# AJH_2b_v1_01.net
KiCad netlist of a schematic drawn in EAGLE
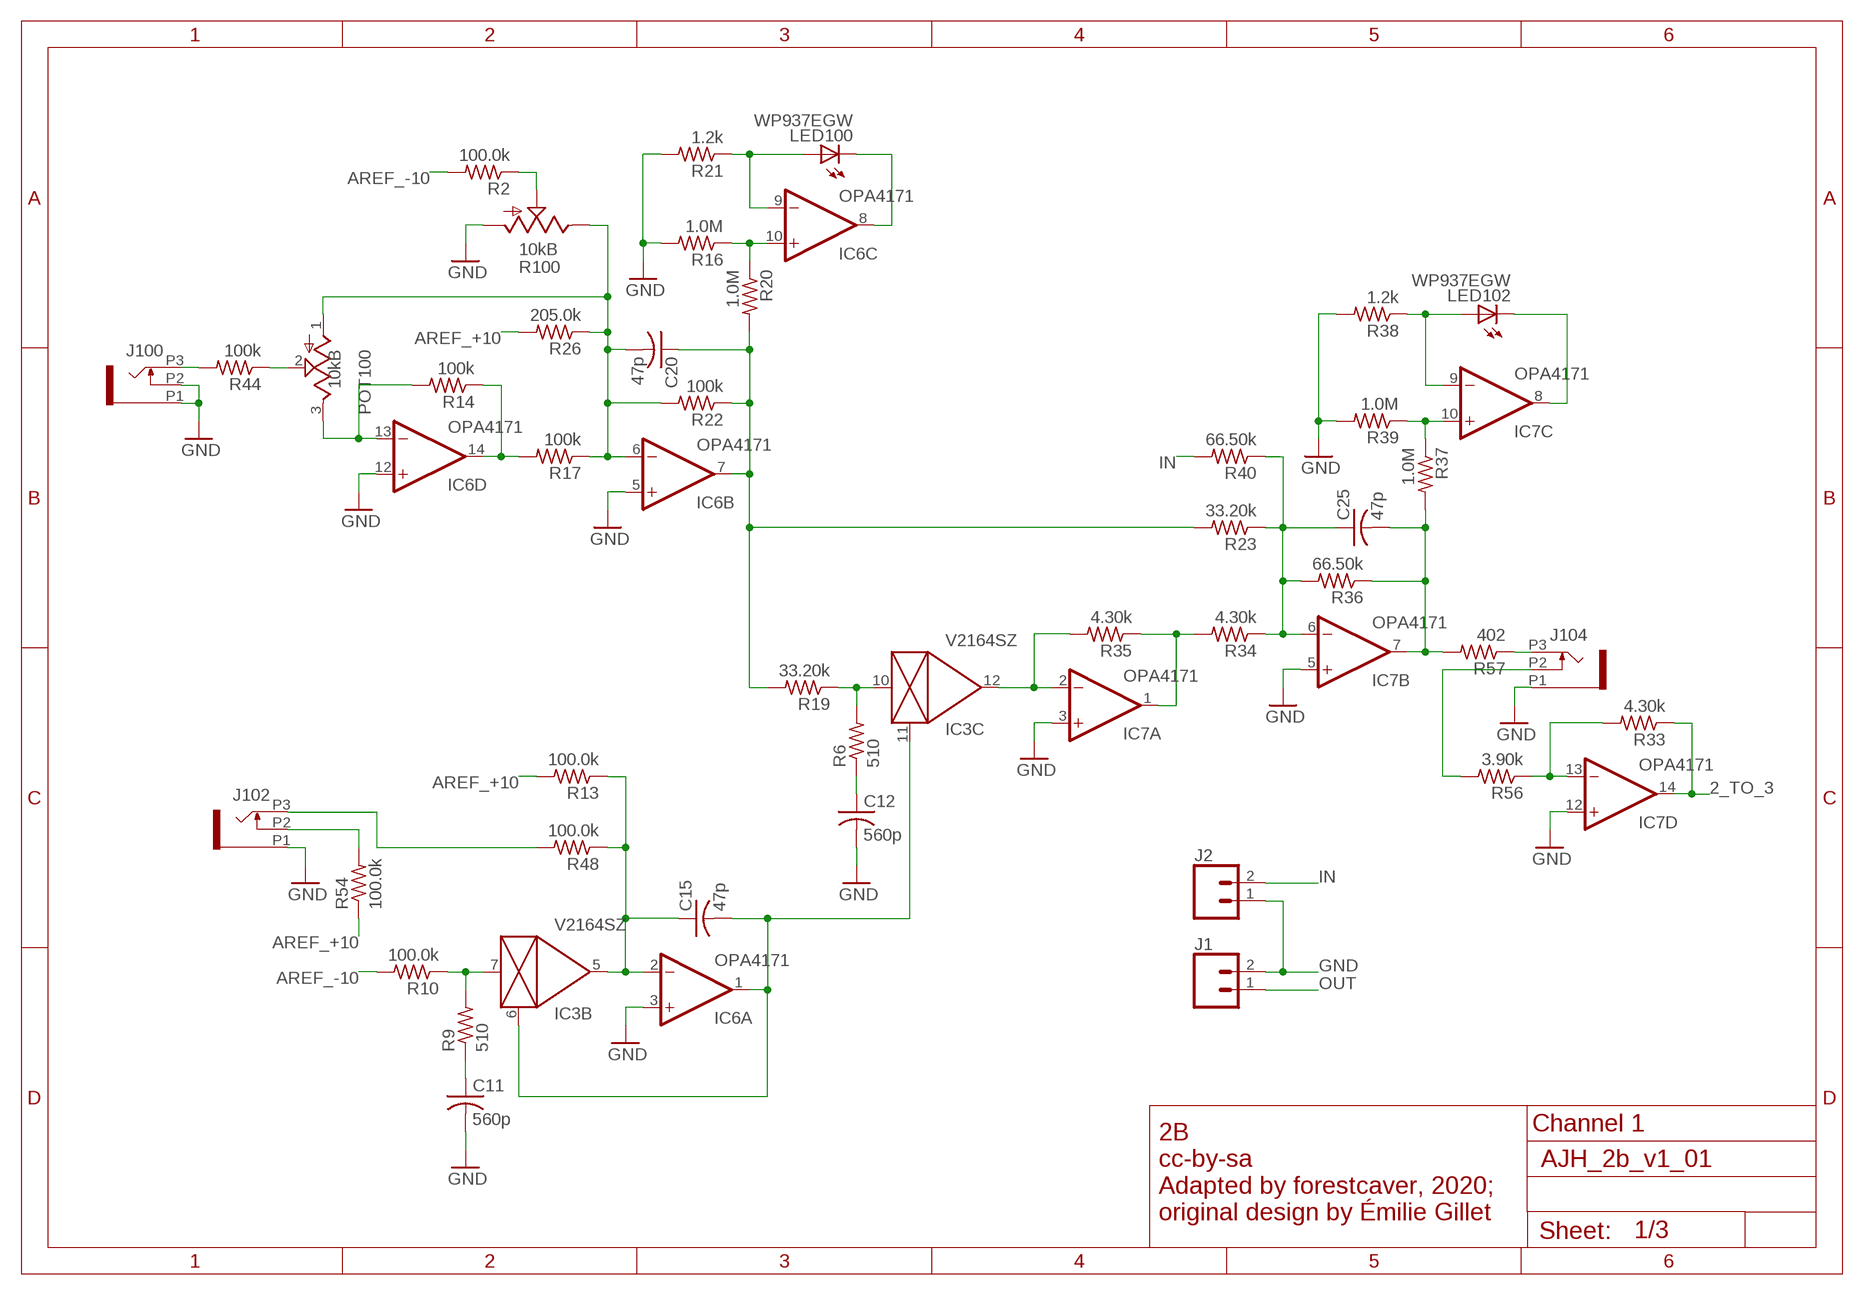
[diagram p0: schematic, sheet 1]
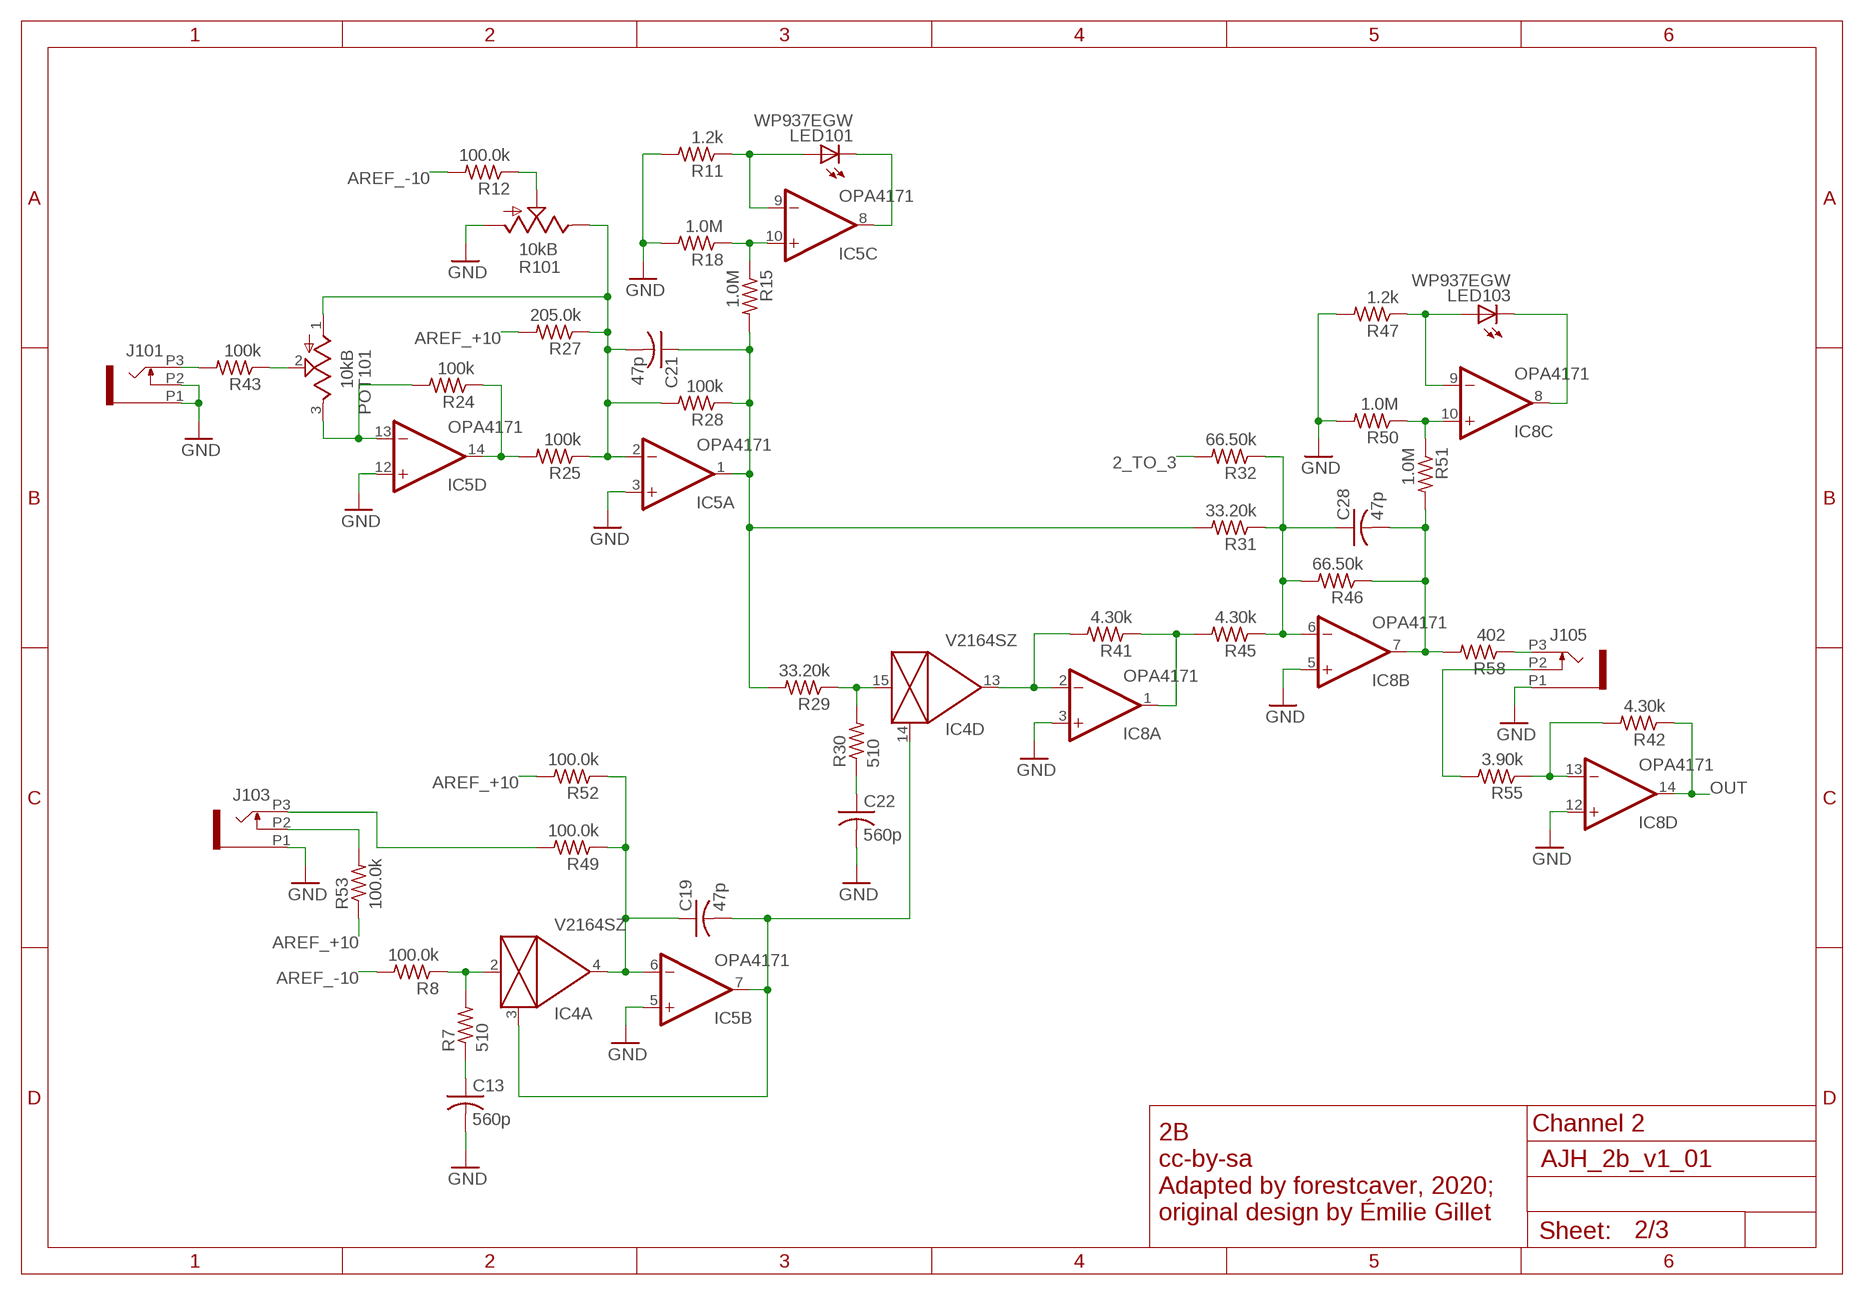
[diagram p1: schematic, sheet 2]
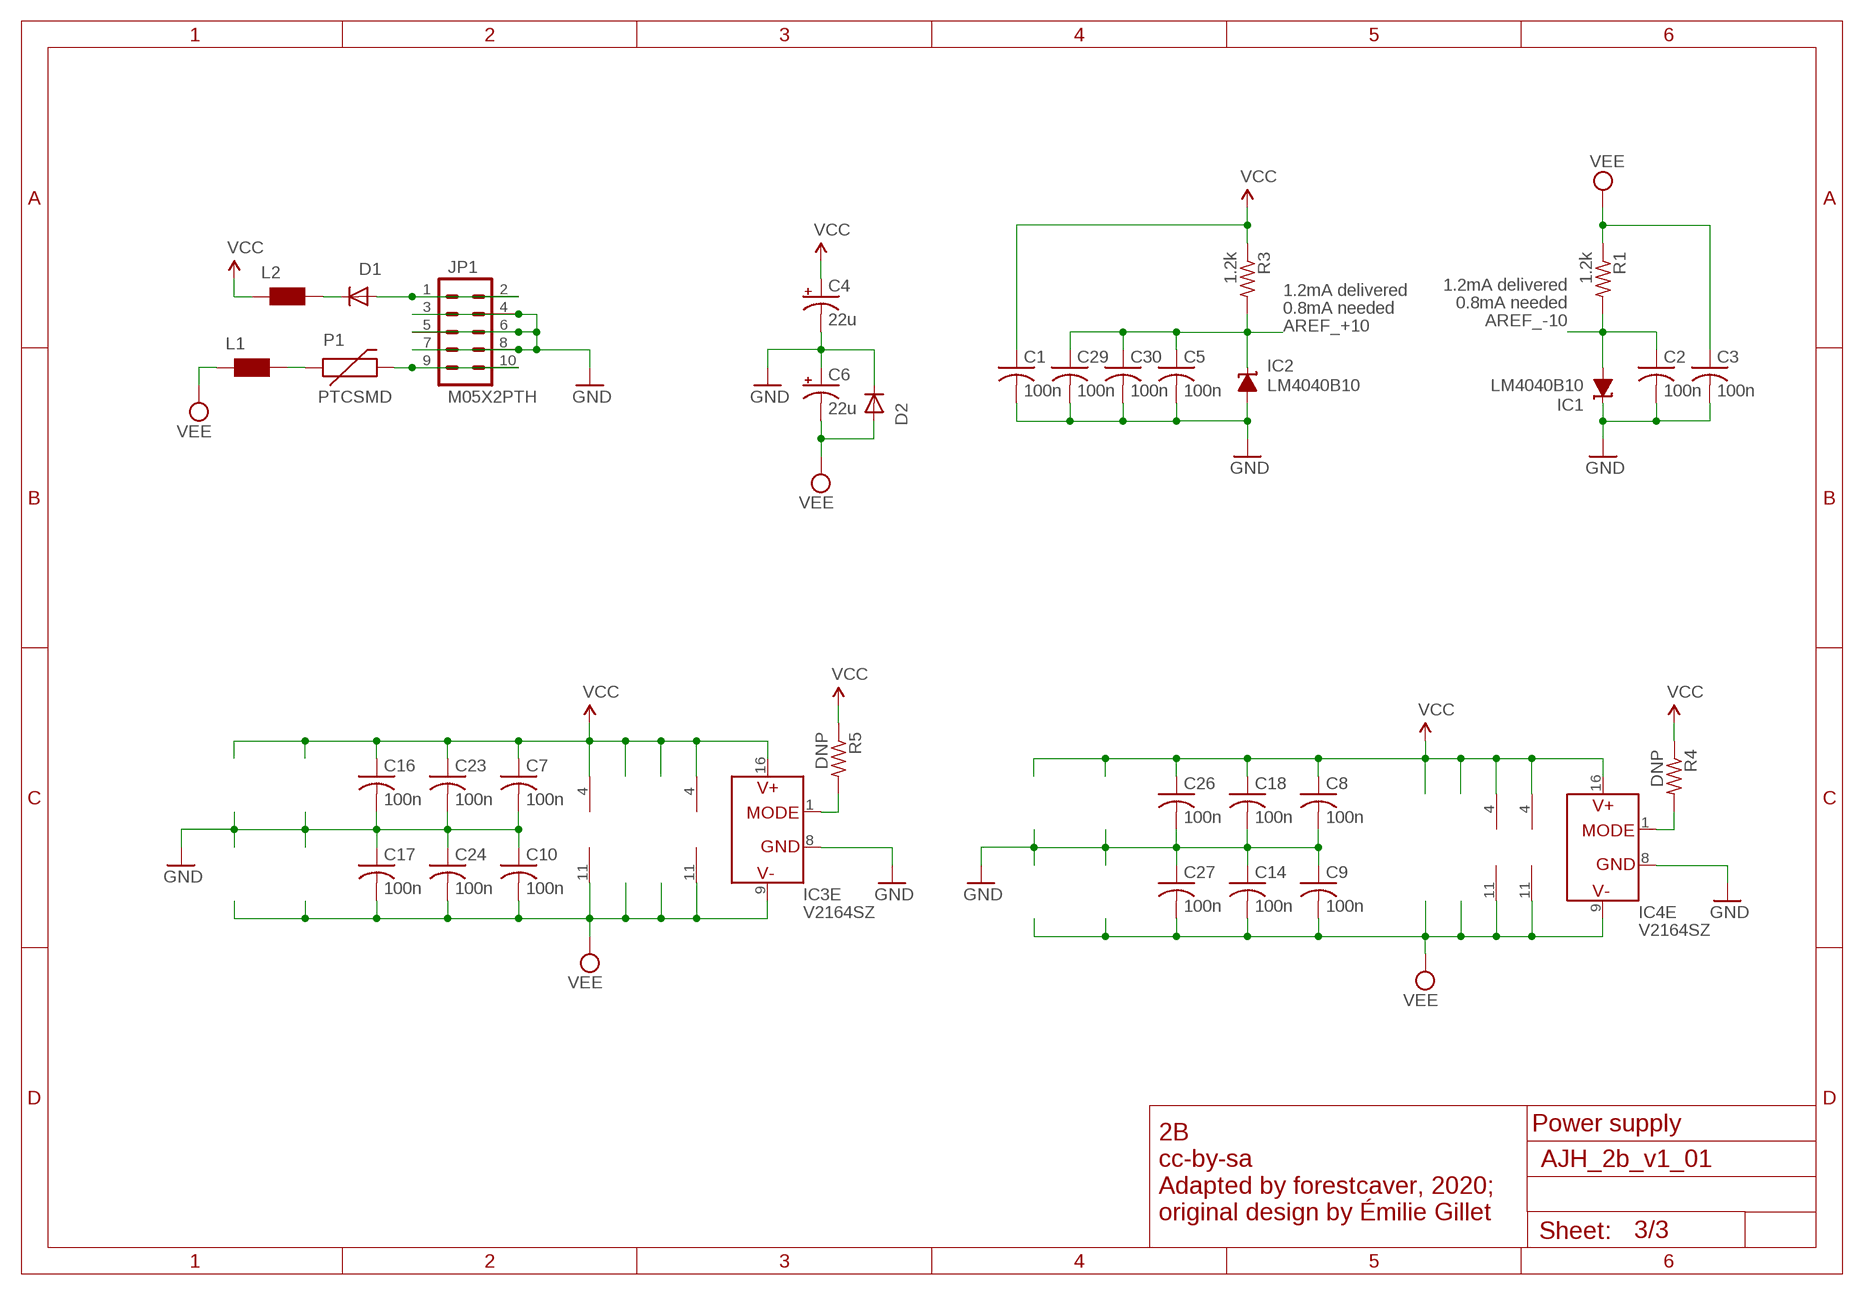
[diagram p2: schematic, sheet 3]

(export (version "E")
  (design (tool "Eeschema 10.0.6"))
  (components
    (comp (ref "C13")
      (value "560p")
      (footprint "eagle-import:C0402")
      (libsource (lib "eagle-import") (part "C-USC0402"))
    )
    (comp (ref "C19")
      (value "47p")
      (footprint "eagle-import:C0402")
      (libsource (lib "eagle-import") (part "C-USC0402"))
    )
    (comp (ref "C21")
      (value "47p")
      (footprint "eagle-import:C0402")
      (libsource (lib "eagle-import") (part "C-USC0402"))
    )
    (comp (ref "C22")
      (value "560p")
      (footprint "eagle-import:C0402")
      (libsource (lib "eagle-import") (part "C-USC0402"))
    )
    (comp (ref "C28")
      (value "47p")
      (footprint "eagle-import:C0402")
      (libsource (lib "eagle-import") (part "C-USC0402"))
    )
    (comp (ref "IC4")
      (value "V2164SZ")
      (footprint "eagle-import:SOIC16N")
      (libsource (lib "eagle-import") (part "SSM2164S"))
    )
    (comp (ref "IC5")
      (value "OPA4171")
      (footprint "eagle-import:TSSOP14")
      (libsource (lib "eagle-import") (part "TL074PW"))
    )
    (comp (ref "IC8")
      (value "OPA4171")
      (footprint "eagle-import:TSSOP14")
      (libsource (lib "eagle-import") (part "TL074PW"))
    )
    (comp (ref "J101")
      (value "PJ301_THONKICONN6")
      (footprint "eagle-import:WQP_PJ_301M6")
      (libsource (lib "eagle-import") (part "PJ301_THONKICONN6"))
    )
    (comp (ref "J103")
      (value "PJ301_THONKICONN6")
      (footprint "eagle-import:WQP_PJ_301M6")
      (libsource (lib "eagle-import") (part "PJ301_THONKICONN6"))
    )
    (comp (ref "J105")
      (value "PJ301_THONKICONN6")
      (footprint "eagle-import:WQP_PJ_301M6")
      (libsource (lib "eagle-import") (part "PJ301_THONKICONN6"))
    )
    (comp (ref "LED101")
      (value "WP937EGW")
      (footprint "eagle-import:LED3MM")
      (libsource (lib "eagle-import") (part "LED3MM"))
    )
    (comp (ref "LED103")
      (value "WP937EGW")
      (footprint "eagle-import:LED3MM")
      (libsource (lib "eagle-import") (part "LED3MM"))
    )
    (comp (ref "POT101")
      (value "10kB")
      (footprint "eagle-import:ALPS_POT_NOHOLE")
      (libsource (lib "eagle-import") (part "POT_VERTICALNOHOLE"))
    )
    (comp (ref "R7")
      (value "510")
      (footprint "eagle-import:R0402")
      (libsource (lib "eagle-import") (part "R-US_R0402"))
    )
    (comp (ref "R8")
      (value "100.0k")
      (footprint "eagle-import:R0402")
      (libsource (lib "eagle-import") (part "R-US_R0402"))
    )
    (comp (ref "R11")
      (value "1.2k")
      (footprint "eagle-import:R0402")
      (libsource (lib "eagle-import") (part "R-US_R0402"))
    )
    (comp (ref "R12")
      (value "100.0k")
      (footprint "eagle-import:R0402")
      (libsource (lib "eagle-import") (part "R-US_R0402"))
    )
    (comp (ref "R15")
      (value "1.0M")
      (footprint "eagle-import:R0402")
      (libsource (lib "eagle-import") (part "R-US_R0402"))
    )
    (comp (ref "R18")
      (value "1.0M")
      (footprint "eagle-import:R0402")
      (libsource (lib "eagle-import") (part "R-US_R0402"))
    )
    (comp (ref "R24")
      (value "100k")
      (footprint "eagle-import:R0402")
      (libsource (lib "eagle-import") (part "R-US_R0402"))
    )
    (comp (ref "R25")
      (value "100k")
      (footprint "eagle-import:R0402")
      (libsource (lib "eagle-import") (part "R-US_R0402"))
    )
    (comp (ref "R27")
      (value "205.0k")
      (footprint "eagle-import:R0402")
      (libsource (lib "eagle-import") (part "R-US_R0402"))
    )
    (comp (ref "R28")
      (value "100k")
      (footprint "eagle-import:R0402")
      (libsource (lib "eagle-import") (part "R-US_R0402"))
    )
    (comp (ref "R29")
      (value "33.20k")
      (footprint "eagle-import:R0402")
      (libsource (lib "eagle-import") (part "R-US_R0402"))
    )
    (comp (ref "R30")
      (value "510")
      (footprint "eagle-import:R0402")
      (libsource (lib "eagle-import") (part "R-US_R0402"))
    )
    (comp (ref "R31")
      (value "33.20k")
      (footprint "eagle-import:R0402")
      (libsource (lib "eagle-import") (part "R-US_R0402"))
    )
    (comp (ref "R32")
      (value "66.50k")
      (footprint "eagle-import:R0402")
      (libsource (lib "eagle-import") (part "R-US_R0402"))
    )
    (comp (ref "R41")
      (value "4.30k")
      (footprint "eagle-import:R0402")
      (libsource (lib "eagle-import") (part "R-US_R0402"))
    )
    (comp (ref "R42")
      (value "4.30k")
      (footprint "eagle-import:R0402")
      (libsource (lib "eagle-import") (part "R-US_R0402"))
    )
    (comp (ref "R43")
      (value "100k")
      (footprint "eagle-import:R0402")
      (libsource (lib "eagle-import") (part "R-US_R0402"))
    )
    (comp (ref "R45")
      (value "4.30k")
      (footprint "eagle-import:R0402")
      (libsource (lib "eagle-import") (part "R-US_R0402"))
    )
    (comp (ref "R46")
      (value "66.50k")
      (footprint "eagle-import:R0402")
      (libsource (lib "eagle-import") (part "R-US_R0402"))
    )
    (comp (ref "R47")
      (value "1.2k")
      (footprint "eagle-import:R0402")
      (libsource (lib "eagle-import") (part "R-US_R0402"))
    )
    (comp (ref "R49")
      (value "100.0k")
      (footprint "eagle-import:R0402")
      (libsource (lib "eagle-import") (part "R-US_R0402"))
    )
    (comp (ref "R50")
      (value "1.0M")
      (footprint "eagle-import:R0402")
      (libsource (lib "eagle-import") (part "R-US_R0402"))
    )
    (comp (ref "R51")
      (value "1.0M")
      (footprint "eagle-import:R0402")
      (libsource (lib "eagle-import") (part "R-US_R0402"))
    )
    (comp (ref "R52")
      (value "100.0k")
      (footprint "eagle-import:R0402")
      (libsource (lib "eagle-import") (part "R-US_R0402"))
    )
    (comp (ref "R53")
      (value "100.0k")
      (footprint "eagle-import:R0402")
      (libsource (lib "eagle-import") (part "R-US_R0402"))
    )
    (comp (ref "R55")
      (value "3.90k")
      (footprint "eagle-import:R0402")
      (libsource (lib "eagle-import") (part "R-US_R0402"))
    )
    (comp (ref "R58")
      (value "402")
      (footprint "eagle-import:R0402")
      (libsource (lib "eagle-import") (part "R-US_R0402"))
    )
    (comp (ref "R101")
      (value "10kB")
      (footprint "eagle-import:ALPS_POT_VERTICAL_PS")
      (libsource (lib "eagle-import") (part "POT_USVERTICAL_PS"))
    )
    (comp (ref "C11")
      (value "560p")
      (footprint "eagle-import:C0402")
      (libsource (lib "eagle-import") (part "C-USC0402"))
    )
    (comp (ref "C12")
      (value "560p")
      (footprint "eagle-import:C0402")
      (libsource (lib "eagle-import") (part "C-USC0402"))
    )
    (comp (ref "C15")
      (value "47p")
      (footprint "eagle-import:C0402")
      (libsource (lib "eagle-import") (part "C-USC0402"))
    )
    (comp (ref "C20")
      (value "47p")
      (footprint "eagle-import:C0402")
      (libsource (lib "eagle-import") (part "C-USC0402"))
    )
    (comp (ref "C25")
      (value "47p")
      (footprint "eagle-import:C0402")
      (libsource (lib "eagle-import") (part "C-USC0402"))
    )
    (comp (ref "IC3")
      (value "V2164SZ")
      (footprint "eagle-import:SOIC16N")
      (libsource (lib "eagle-import") (part "SSM2164S"))
    )
    (comp (ref "IC6")
      (value "OPA4171")
      (footprint "eagle-import:TSSOP14")
      (libsource (lib "eagle-import") (part "TL074PW"))
    )
    (comp (ref "IC7")
      (value "OPA4171")
      (footprint "eagle-import:TSSOP14")
      (libsource (lib "eagle-import") (part "TL074PW"))
    )
    (comp (ref "J1")
      (value "CONN_02")
      (footprint "eagle-import:1X02")
      (libsource (lib "eagle-import") (part "CONN_02"))
    )
    (comp (ref "J2")
      (value "CONN_02")
      (footprint "eagle-import:1X02")
      (libsource (lib "eagle-import") (part "CONN_02"))
    )
    (comp (ref "J100")
      (value "PJ301_THONKICONN6")
      (footprint "eagle-import:WQP_PJ_301M6")
      (libsource (lib "eagle-import") (part "PJ301_THONKICONN6"))
    )
    (comp (ref "J102")
      (value "PJ301_THONKICONN6")
      (footprint "eagle-import:WQP_PJ_301M6")
      (libsource (lib "eagle-import") (part "PJ301_THONKICONN6"))
    )
    (comp (ref "J104")
      (value "PJ301_THONKICONN6")
      (footprint "eagle-import:WQP_PJ_301M6")
      (libsource (lib "eagle-import") (part "PJ301_THONKICONN6"))
    )
    (comp (ref "LED100")
      (value "WP937EGW")
      (footprint "eagle-import:LED3MM")
      (libsource (lib "eagle-import") (part "LED3MM"))
    )
    (comp (ref "LED102")
      (value "WP937EGW")
      (footprint "eagle-import:LED3MM")
      (libsource (lib "eagle-import") (part "LED3MM"))
    )
    (comp (ref "POT100")
      (value "10kB")
      (footprint "eagle-import:ALPS_POT_NOHOLE")
      (libsource (lib "eagle-import") (part "POT_VERTICALNOHOLE"))
    )
    (comp (ref "R2")
      (value "100.0k")
      (footprint "eagle-import:R0402")
      (libsource (lib "eagle-import") (part "R-US_R0402"))
    )
    (comp (ref "R6")
      (value "510")
      (footprint "eagle-import:R0402")
      (libsource (lib "eagle-import") (part "R-US_R0402"))
    )
    (comp (ref "R9")
      (value "510")
      (footprint "eagle-import:R0402")
      (libsource (lib "eagle-import") (part "R-US_R0402"))
    )
    (comp (ref "R10")
      (value "100.0k")
      (footprint "eagle-import:R0402")
      (libsource (lib "eagle-import") (part "R-US_R0402"))
    )
    (comp (ref "R13")
      (value "100.0k")
      (footprint "eagle-import:R0402")
      (libsource (lib "eagle-import") (part "R-US_R0402"))
    )
    (comp (ref "R14")
      (value "100k")
      (footprint "eagle-import:R0402")
      (libsource (lib "eagle-import") (part "R-US_R0402"))
    )
    (comp (ref "R16")
      (value "1.0M")
      (footprint "eagle-import:R0402")
      (libsource (lib "eagle-import") (part "R-US_R0402"))
    )
    (comp (ref "R17")
      (value "100k")
      (footprint "eagle-import:R0402")
      (libsource (lib "eagle-import") (part "R-US_R0402"))
    )
    (comp (ref "R19")
      (value "33.20k")
      (footprint "eagle-import:R0402")
      (libsource (lib "eagle-import") (part "R-US_R0402"))
    )
    (comp (ref "R20")
      (value "1.0M")
      (footprint "eagle-import:R0402")
      (libsource (lib "eagle-import") (part "R-US_R0402"))
    )
    (comp (ref "R21")
      (value "1.2k")
      (footprint "eagle-import:R0402")
      (libsource (lib "eagle-import") (part "R-US_R0402"))
    )
    (comp (ref "R22")
      (value "100k")
      (footprint "eagle-import:R0402")
      (libsource (lib "eagle-import") (part "R-US_R0402"))
    )
    (comp (ref "R23")
      (value "33.20k")
      (footprint "eagle-import:R0402")
      (libsource (lib "eagle-import") (part "R-US_R0402"))
    )
    (comp (ref "R26")
      (value "205.0k")
      (footprint "eagle-import:R0402")
      (libsource (lib "eagle-import") (part "R-US_R0402"))
    )
    (comp (ref "R33")
      (value "4.30k")
      (footprint "eagle-import:R0402")
      (libsource (lib "eagle-import") (part "R-US_R0402"))
    )
    (comp (ref "R34")
      (value "4.30k")
      (footprint "eagle-import:R0402")
      (libsource (lib "eagle-import") (part "R-US_R0402"))
    )
    (comp (ref "R35")
      (value "4.30k")
      (footprint "eagle-import:R0402")
      (libsource (lib "eagle-import") (part "R-US_R0402"))
    )
    (comp (ref "R36")
      (value "66.50k")
      (footprint "eagle-import:R0402")
      (libsource (lib "eagle-import") (part "R-US_R0402"))
    )
    (comp (ref "R37")
      (value "1.0M")
      (footprint "eagle-import:R0402")
      (libsource (lib "eagle-import") (part "R-US_R0402"))
    )
    (comp (ref "R38")
      (value "1.2k")
      (footprint "eagle-import:R0402")
      (libsource (lib "eagle-import") (part "R-US_R0402"))
    )
    (comp (ref "R39")
      (value "1.0M")
      (footprint "eagle-import:R0402")
      (libsource (lib "eagle-import") (part "R-US_R0402"))
    )
    (comp (ref "R40")
      (value "66.50k")
      (footprint "eagle-import:R0402")
      (libsource (lib "eagle-import") (part "R-US_R0402"))
    )
    (comp (ref "R44")
      (value "100k")
      (footprint "eagle-import:R0402")
      (libsource (lib "eagle-import") (part "R-US_R0402"))
    )
    (comp (ref "R48")
      (value "100.0k")
      (footprint "eagle-import:R0402")
      (libsource (lib "eagle-import") (part "R-US_R0402"))
    )
    (comp (ref "R54")
      (value "100.0k")
      (footprint "eagle-import:R0402")
      (libsource (lib "eagle-import") (part "R-US_R0402"))
    )
    (comp (ref "R56")
      (value "3.90k")
      (footprint "eagle-import:R0402")
      (libsource (lib "eagle-import") (part "R-US_R0402"))
    )
    (comp (ref "R57")
      (value "402")
      (footprint "eagle-import:R0402")
      (libsource (lib "eagle-import") (part "R-US_R0402"))
    )
    (comp (ref "R100")
      (value "10kB")
      (footprint "eagle-import:ALPS_POT_VERTICAL_PS")
      (libsource (lib "eagle-import") (part "POT_USVERTICAL_PS"))
    )
    (comp (ref "C1")
      (value "100n")
      (footprint "eagle-import:C0402")
      (libsource (lib "eagle-import") (part "C-USC0402"))
    )
    (comp (ref "C2")
      (value "100n")
      (footprint "eagle-import:C0402")
      (libsource (lib "eagle-import") (part "C-USC0402"))
    )
    (comp (ref "C3")
      (value "100n")
      (footprint "eagle-import:C0402")
      (libsource (lib "eagle-import") (part "C-USC0402"))
    )
    (comp (ref "C4")
      (value "22u")
      (footprint "eagle-import:PANASONIC_B")
      (libsource (lib "eagle-import") (part "CPOL-USB"))
    )
    (comp (ref "C5")
      (value "100n")
      (footprint "eagle-import:C0402")
      (libsource (lib "eagle-import") (part "C-USC0402"))
    )
    (comp (ref "C6")
      (value "22u")
      (footprint "eagle-import:PANASONIC_B")
      (libsource (lib "eagle-import") (part "CPOL-USB"))
    )
    (comp (ref "C7")
      (value "100n")
      (footprint "eagle-import:C0402")
      (libsource (lib "eagle-import") (part "C-USC0402"))
    )
    (comp (ref "C8")
      (value "100n")
      (footprint "eagle-import:C0402")
      (libsource (lib "eagle-import") (part "C-USC0402"))
    )
    (comp (ref "C9")
      (value "100n")
      (footprint "eagle-import:C0402")
      (libsource (lib "eagle-import") (part "C-USC0402"))
    )
    (comp (ref "C10")
      (value "100n")
      (footprint "eagle-import:C0402")
      (libsource (lib "eagle-import") (part "C-USC0402"))
    )
    (comp (ref "C14")
      (value "100n")
      (footprint "eagle-import:C0402")
      (libsource (lib "eagle-import") (part "C-USC0402"))
    )
    (comp (ref "C16")
      (value "100n")
      (footprint "eagle-import:C0402")
      (libsource (lib "eagle-import") (part "C-USC0402"))
    )
    (comp (ref "C17")
      (value "100n")
      (footprint "eagle-import:C0402")
      (libsource (lib "eagle-import") (part "C-USC0402"))
    )
    (comp (ref "C18")
      (value "100n")
      (footprint "eagle-import:C0402")
      (libsource (lib "eagle-import") (part "C-USC0402"))
    )
    (comp (ref "C23")
      (value "100n")
      (footprint "eagle-import:C0402")
      (libsource (lib "eagle-import") (part "C-USC0402"))
    )
    (comp (ref "C24")
      (value "100n")
      (footprint "eagle-import:C0402")
      (libsource (lib "eagle-import") (part "C-USC0402"))
    )
    (comp (ref "C26")
      (value "100n")
      (footprint "eagle-import:C0402")
      (libsource (lib "eagle-import") (part "C-USC0402"))
    )
    (comp (ref "C27")
      (value "100n")
      (footprint "eagle-import:C0402")
      (libsource (lib "eagle-import") (part "C-USC0402"))
    )
    (comp (ref "C29")
      (value "100n")
      (footprint "eagle-import:C0402")
      (libsource (lib "eagle-import") (part "C-USC0402"))
    )
    (comp (ref "C30")
      (value "100n")
      (footprint "eagle-import:C0402")
      (libsource (lib "eagle-import") (part "C-USC0402"))
    )
    (comp (ref "D1")
      (value "1N5819HW")
      (footprint "eagle-import:SOD123")
      (libsource (lib "eagle-import") (part "DIODE-SOD123"))
    )
    (comp (ref "D2")
      (value "1N5819HW")
      (footprint "eagle-import:SOD123")
      (libsource (lib "eagle-import") (part "DIODE-SOD123"))
    )
    (comp (ref "IC1")
      (value "LM4040B10")
      (footprint "eagle-import:DBZ_R-PDSO-G3")
      (libsource (lib "eagle-import") (part "LM4041DBZB12"))
    )
    (comp (ref "IC2")
      (value "LM4040B10")
      (footprint "eagle-import:DBZ_R-PDSO-G3")
      (libsource (lib "eagle-import") (part "LM4041DBZB12"))
    )
    (comp (ref "JP1")
      (value "M05X2PTH")
      (footprint "eagle-import:AVR_ICSP")
      (libsource (lib "eagle-import") (part "M05X2PTH"))
    )
    (comp (ref "L1")
      (value "WE-CBF_0603")
      (footprint "eagle-import:0603")
      (libsource (lib "eagle-import") (part "WE-CBF_0603"))
    )
    (comp (ref "L2")
      (value "WE-CBF_0603")
      (footprint "eagle-import:0603")
      (libsource (lib "eagle-import") (part "WE-CBF_0603"))
    )
    (comp (ref "P1")
      (value "PTCSMD")
      (footprint "eagle-import:PTC-1206")
      (libsource (lib "eagle-import") (part "PTCSMD"))
    )
    (comp (ref "R1")
      (value "1.2k")
      (footprint "eagle-import:R0402")
      (libsource (lib "eagle-import") (part "R-US_R0402"))
    )
    (comp (ref "R3")
      (value "1.2k")
      (footprint "eagle-import:R0402")
      (libsource (lib "eagle-import") (part "R-US_R0402"))
    )
    (comp (ref "R4")
      (value "DNP")
      (footprint "eagle-import:R0402")
      (libsource (lib "eagle-import") (part "R-US_R0402"))
    )
    (comp (ref "R5")
      (value "DNP")
      (footprint "eagle-import:R0402")
      (libsource (lib "eagle-import") (part "R-US_R0402"))
    )
  )
  (nets
    (net (code "1") (name "2_TO_3") (class "Default")
      (node (ref "IC7") (pin "14") (pinfunction "OUT_14") (pintype "output"))
      (node (ref "R32") (pin "2") (pinfunction "2_2") (pintype "passive"))
      (node (ref "R33") (pin "1") (pinfunction "1_1") (pintype "passive"))
    )
    (net (code "2") (name "AREF_+10") (class "Default")
      (node (ref "C29") (pin "1") (pinfunction "1_1") (pintype "passive"))
      (node (ref "C30") (pin "1") (pinfunction "1_1") (pintype "passive"))
      (node (ref "C5") (pin "1") (pinfunction "1_1") (pintype "passive"))
      (node (ref "IC2") (pin "1") (pinfunction "C_1") (pintype "passive"))
      (node (ref "R13") (pin "2") (pinfunction "2_2") (pintype "passive"))
      (node (ref "R26") (pin "2") (pinfunction "2_2") (pintype "passive"))
      (node (ref "R27") (pin "2") (pinfunction "2_2") (pintype "passive"))
      (node (ref "R3") (pin "2") (pinfunction "2_2") (pintype "passive"))
      (node (ref "R52") (pin "2") (pinfunction "2_2") (pintype "passive"))
      (node (ref "R53") (pin "1") (pinfunction "1_1") (pintype "passive"))
      (node (ref "R54") (pin "1") (pinfunction "1_1") (pintype "passive"))
    )
    (net (code "3") (name "AREF_-10") (class "Default")
      (node (ref "C2") (pin "1") (pinfunction "1_1") (pintype "passive"))
      (node (ref "IC1") (pin "2") (pinfunction "A_2") (pintype "passive"))
      (node (ref "R1") (pin "2") (pinfunction "2_2") (pintype "passive"))
      (node (ref "R10") (pin "2") (pinfunction "2_2") (pintype "passive"))
      (node (ref "R12") (pin "2") (pinfunction "2_2") (pintype "passive"))
      (node (ref "R2") (pin "2") (pinfunction "2_2") (pintype "passive"))
      (node (ref "R8") (pin "2") (pinfunction "2_2") (pintype "passive"))
    )
    (net (code "4") (name "GND") (class "Default")
      (node (ref "C1") (pin "2") (pinfunction "2_2") (pintype "passive"))
      (node (ref "C10") (pin "1") (pinfunction "1_1") (pintype "passive"))
      (node (ref "C11") (pin "2") (pinfunction "2_2") (pintype "passive"))
      (node (ref "C12") (pin "2") (pinfunction "2_2") (pintype "passive"))
      (node (ref "C13") (pin "2") (pinfunction "2_2") (pintype "passive"))
      (node (ref "C14") (pin "1") (pinfunction "1_1") (pintype "passive"))
      (node (ref "C16") (pin "2") (pinfunction "2_2") (pintype "passive"))
      (node (ref "C17") (pin "1") (pinfunction "1_1") (pintype "passive"))
      (node (ref "C18") (pin "2") (pinfunction "2_2") (pintype "passive"))
      (node (ref "C2") (pin "2") (pinfunction "2_2") (pintype "passive"))
      (node (ref "C22") (pin "2") (pinfunction "2_2") (pintype "passive"))
      (node (ref "C23") (pin "2") (pinfunction "2_2") (pintype "passive"))
      (node (ref "C24") (pin "1") (pinfunction "1_1") (pintype "passive"))
      (node (ref "C26") (pin "2") (pinfunction "2_2") (pintype "passive"))
      (node (ref "C27") (pin "1") (pinfunction "1_1") (pintype "passive"))
      (node (ref "C29") (pin "2") (pinfunction "2_2") (pintype "passive"))
      (node (ref "C3") (pin "2") (pinfunction "2_2") (pintype "passive"))
      (node (ref "C30") (pin "2") (pinfunction "2_2") (pintype "passive"))
      (node (ref "C4") (pin "-") (pinfunction "-_-") (pintype "passive"))
      (node (ref "C5") (pin "2") (pinfunction "2_2") (pintype "passive"))
      (node (ref "C6") (pin "+") (pinfunction "+_+") (pintype "passive"))
      (node (ref "C7") (pin "2") (pinfunction "2_2") (pintype "passive"))
      (node (ref "C8") (pin "2") (pinfunction "2_2") (pintype "passive"))
      (node (ref "C9") (pin "1") (pinfunction "1_1") (pintype "passive"))
      (node (ref "D2") (pin "C") (pinfunction "C_C") (pintype "passive"))
      (node (ref "IC1") (pin "1") (pinfunction "C_1") (pintype "passive"))
      (node (ref "IC2") (pin "2") (pinfunction "A_2") (pintype "passive"))
      (node (ref "IC3") (pin "8") (pinfunction "GND_8") (pintype "power_in"))
      (node (ref "IC4") (pin "8") (pinfunction "GND_8") (pintype "power_in"))
      (node (ref "IC5") (pin "12") (pinfunction "+IN_12") (pintype "input"))
      (node (ref "IC5") (pin "3") (pinfunction "+IN_3") (pintype "input"))
      (node (ref "IC5") (pin "5") (pinfunction "+IN_5") (pintype "input"))
      (node (ref "IC6") (pin "12") (pinfunction "+IN_12") (pintype "input"))
      (node (ref "IC6") (pin "3") (pinfunction "+IN_3") (pintype "input"))
      (node (ref "IC6") (pin "5") (pinfunction "+IN_5") (pintype "input"))
      (node (ref "IC7") (pin "12") (pinfunction "+IN_12") (pintype "input"))
      (node (ref "IC7") (pin "3") (pinfunction "+IN_3") (pintype "input"))
      (node (ref "IC7") (pin "5") (pinfunction "+IN_5") (pintype "input"))
      (node (ref "IC8") (pin "12") (pinfunction "+IN_12") (pintype "input"))
      (node (ref "IC8") (pin "3") (pinfunction "+IN_3") (pintype "input"))
      (node (ref "IC8") (pin "5") (pinfunction "+IN_5") (pintype "input"))
      (node (ref "J1") (pin "2") (pinfunction "2_2") (pintype "passive"))
      (node (ref "J100") (pin "P1") (pinfunction "1_P1") (pintype "passive"))
      (node (ref "J100") (pin "P2") (pinfunction "2_P2") (pintype "passive"))
      (node (ref "J101") (pin "P1") (pinfunction "1_P1") (pintype "passive"))
      (node (ref "J101") (pin "P2") (pinfunction "2_P2") (pintype "passive"))
      (node (ref "J102") (pin "P1") (pinfunction "1_P1") (pintype "passive"))
      (node (ref "J103") (pin "P1") (pinfunction "1_P1") (pintype "passive"))
      (node (ref "J104") (pin "P1") (pinfunction "1_P1") (pintype "passive"))
      (node (ref "J105") (pin "P1") (pinfunction "1_P1") (pintype "passive"))
      (node (ref "J2") (pin "1") (pinfunction "1_1") (pintype "passive"))
      (node (ref "JP1") (pin "3") (pinfunction "3_3") (pintype "passive"))
      (node (ref "JP1") (pin "4") (pinfunction "4_4") (pintype "passive"))
      (node (ref "JP1") (pin "5") (pinfunction "5_5") (pintype "passive"))
      (node (ref "JP1") (pin "6") (pinfunction "6_6") (pintype "passive"))
      (node (ref "JP1") (pin "7") (pinfunction "7_7") (pintype "passive"))
      (node (ref "JP1") (pin "8") (pinfunction "8_8") (pintype "passive"))
      (node (ref "R100") (pin "P$3") (pinfunction "A_P$3") (pintype "passive"))
      (node (ref "R101") (pin "P$3") (pinfunction "A_P$3") (pintype "passive"))
      (node (ref "R11") (pin "2") (pinfunction "2_2") (pintype "passive"))
      (node (ref "R16") (pin "2") (pinfunction "2_2") (pintype "passive"))
      (node (ref "R18") (pin "2") (pinfunction "2_2") (pintype "passive"))
      (node (ref "R21") (pin "2") (pinfunction "2_2") (pintype "passive"))
      (node (ref "R38") (pin "2") (pinfunction "2_2") (pintype "passive"))
      (node (ref "R39") (pin "2") (pinfunction "2_2") (pintype "passive"))
      (node (ref "R47") (pin "2") (pinfunction "2_2") (pintype "passive"))
      (node (ref "R50") (pin "2") (pinfunction "2_2") (pintype "passive"))
    )
    (net (code "5") (name "IN") (class "Default")
      (node (ref "J2") (pin "2") (pinfunction "2_2") (pintype "passive"))
      (node (ref "R40") (pin "2") (pinfunction "2_2") (pintype "passive"))
    )
    (net (code "6") (name "Net-(C11-Pad1)") (class "Default")
      (node (ref "C11") (pin "1") (pinfunction "1_1") (pintype "passive"))
      (node (ref "R9") (pin "1") (pinfunction "1_1") (pintype "passive"))
    )
    (net (code "7") (name "Net-(C12-Pad1)") (class "Default")
      (node (ref "C12") (pin "1") (pinfunction "1_1") (pintype "passive"))
      (node (ref "R6") (pin "1") (pinfunction "1_1") (pintype "passive"))
    )
    (net (code "8") (name "Net-(C13-Pad1)") (class "Default")
      (node (ref "C13") (pin "1") (pinfunction "1_1") (pintype "passive"))
      (node (ref "R7") (pin "1") (pinfunction "1_1") (pintype "passive"))
    )
    (net (code "9") (name "Net-(C22-Pad1)") (class "Default")
      (node (ref "C22") (pin "1") (pinfunction "1_1") (pintype "passive"))
      (node (ref "R30") (pin "1") (pinfunction "1_1") (pintype "passive"))
    )
    (net (code "10") (name "Net-(D1-PadA)") (class "Default")
      (node (ref "D1") (pin "A") (pinfunction "A_A") (pintype "passive"))
      (node (ref "JP1") (pin "1") (pinfunction "1_1") (pintype "passive"))
      (node (ref "JP1") (pin "2") (pinfunction "2_2") (pintype "passive"))
    )
    (net (code "11") (name "Net-(D1-PadC)") (class "Default")
      (node (ref "D1") (pin "C") (pinfunction "C_C") (pintype "passive"))
      (node (ref "L2") (pin "2") (pinfunction "2_2") (pintype "passive"))
    )
    (net (code "12") (name "Net-(IC3B-CTRL)") (class "Default")
      (node (ref "C15") (pin "2") (pinfunction "2_2") (pintype "passive"))
      (node (ref "IC3") (pin "11") (pinfunction "CTRL_11") (pintype "input"))
      (node (ref "IC3") (pin "6") (pinfunction "CTRL_6") (pintype "input"))
      (node (ref "IC6") (pin "1") (pinfunction "OUT_1") (pintype "output"))
    )
    (net (code "13") (name "Net-(IC3B-IN)") (class "Default")
      (node (ref "IC3") (pin "7") (pinfunction "IN_7") (pintype "input"))
      (node (ref "R10") (pin "1") (pinfunction "1_1") (pintype "passive"))
      (node (ref "R9") (pin "2") (pinfunction "2_2") (pintype "passive"))
    )
    (net (code "14") (name "Net-(IC3B-OUT)") (class "Default")
      (node (ref "C15") (pin "1") (pinfunction "1_1") (pintype "passive"))
      (node (ref "IC3") (pin "5") (pinfunction "OUT_5") (pintype "output"))
      (node (ref "IC6") (pin "2") (pinfunction "-IN_2") (pintype "input"))
      (node (ref "R13") (pin "1") (pinfunction "1_1") (pintype "passive"))
      (node (ref "R48") (pin "1") (pinfunction "1_1") (pintype "passive"))
    )
    (net (code "15") (name "Net-(IC3C-IN)") (class "Default")
      (node (ref "IC3") (pin "10") (pinfunction "IN_10") (pintype "input"))
      (node (ref "R19") (pin "1") (pinfunction "1_1") (pintype "passive"))
      (node (ref "R6") (pin "2") (pinfunction "2_2") (pintype "passive"))
    )
    (net (code "16") (name "Net-(IC3C-OUT)") (class "Default")
      (node (ref "IC3") (pin "12") (pinfunction "OUT_12") (pintype "output"))
      (node (ref "IC7") (pin "2") (pinfunction "-IN_2") (pintype "input"))
      (node (ref "R35") (pin "2") (pinfunction "2_2") (pintype "passive"))
    )
    (net (code "17") (name "Net-(IC3E-MODE)") (class "Default")
      (node (ref "IC3") (pin "1") (pinfunction "MODE_1") (pintype "input"))
      (node (ref "R5") (pin "2") (pinfunction "2_2") (pintype "passive"))
    )
    (net (code "18") (name "Net-(IC4A-CTRL)") (class "Default")
      (node (ref "C19") (pin "2") (pinfunction "2_2") (pintype "passive"))
      (node (ref "IC4") (pin "14") (pinfunction "CTRL_14") (pintype "input"))
      (node (ref "IC4") (pin "3") (pinfunction "CTRL_3") (pintype "input"))
      (node (ref "IC5") (pin "7") (pinfunction "OUT_7") (pintype "output"))
    )
    (net (code "19") (name "Net-(IC4A-IN)") (class "Default")
      (node (ref "IC4") (pin "2") (pinfunction "IN_2") (pintype "input"))
      (node (ref "R7") (pin "2") (pinfunction "2_2") (pintype "passive"))
      (node (ref "R8") (pin "1") (pinfunction "1_1") (pintype "passive"))
    )
    (net (code "20") (name "Net-(IC4A-OUT)") (class "Default")
      (node (ref "C19") (pin "1") (pinfunction "1_1") (pintype "passive"))
      (node (ref "IC4") (pin "4") (pinfunction "OUT_4") (pintype "output"))
      (node (ref "IC5") (pin "6") (pinfunction "-IN_6") (pintype "input"))
      (node (ref "R49") (pin "1") (pinfunction "1_1") (pintype "passive"))
      (node (ref "R52") (pin "1") (pinfunction "1_1") (pintype "passive"))
    )
    (net (code "21") (name "Net-(IC4D-IN)") (class "Default")
      (node (ref "IC4") (pin "15") (pinfunction "IN_15") (pintype "input"))
      (node (ref "R29") (pin "1") (pinfunction "1_1") (pintype "passive"))
      (node (ref "R30") (pin "2") (pinfunction "2_2") (pintype "passive"))
    )
    (net (code "22") (name "Net-(IC4D-OUT)") (class "Default")
      (node (ref "IC4") (pin "13") (pinfunction "OUT_13") (pintype "output"))
      (node (ref "IC8") (pin "2") (pinfunction "-IN_2") (pintype "input"))
      (node (ref "R41") (pin "2") (pinfunction "2_2") (pintype "passive"))
    )
    (net (code "23") (name "Net-(IC4E-MODE)") (class "Default")
      (node (ref "IC4") (pin "1") (pinfunction "MODE_1") (pintype "input"))
      (node (ref "R4") (pin "2") (pinfunction "2_2") (pintype "passive"))
    )
    (net (code "24") (name "Net-(IC5A--IN)") (class "Default")
      (node (ref "C21") (pin "2") (pinfunction "2_2") (pintype "passive"))
      (node (ref "IC5") (pin "2") (pinfunction "-IN_2") (pintype "input"))
      (node (ref "POT101") (pin "1") (pinfunction "A_1") (pintype "passive"))
      (node (ref "R101") (pin "P$1") (pinfunction "E_P$1") (pintype "passive"))
      (node (ref "R25") (pin "1") (pinfunction "1_1") (pintype "passive"))
      (node (ref "R27") (pin "1") (pinfunction "1_1") (pintype "passive"))
      (node (ref "R28") (pin "2") (pinfunction "2_2") (pintype "passive"))
    )
    (net (code "25") (name "Net-(IC5A-OUT)") (class "Default")
      (node (ref "C21") (pin "1") (pinfunction "1_1") (pintype "passive"))
      (node (ref "IC5") (pin "1") (pinfunction "OUT_1") (pintype "output"))
      (node (ref "R15") (pin "2") (pinfunction "2_2") (pintype "passive"))
      (node (ref "R28") (pin "1") (pinfunction "1_1") (pintype "passive"))
      (node (ref "R29") (pin "2") (pinfunction "2_2") (pintype "passive"))
      (node (ref "R31") (pin "2") (pinfunction "2_2") (pintype "passive"))
    )
    (net (code "26") (name "Net-(IC5C-+IN)") (class "Default")
      (node (ref "IC5") (pin "10") (pinfunction "+IN_10") (pintype "input"))
      (node (ref "R15") (pin "1") (pinfunction "1_1") (pintype "passive"))
      (node (ref "R18") (pin "1") (pinfunction "1_1") (pintype "passive"))
    )
    (net (code "27") (name "Net-(IC5C--IN)") (class "Default")
      (node (ref "IC5") (pin "9") (pinfunction "-IN_9") (pintype "input"))
      (node (ref "LED101") (pin "A") (pinfunction "A_A") (pintype "passive"))
      (node (ref "R11") (pin "1") (pinfunction "1_1") (pintype "passive"))
    )
    (net (code "28") (name "Net-(IC5C-OUT)") (class "Default")
      (node (ref "IC5") (pin "8") (pinfunction "OUT_8") (pintype "output"))
      (node (ref "LED101") (pin "K") (pinfunction "C_K") (pintype "passive"))
    )
    (net (code "29") (name "Net-(IC5D--IN)") (class "Default")
      (node (ref "IC5") (pin "13") (pinfunction "-IN_13") (pintype "input"))
      (node (ref "POT101") (pin "3") (pinfunction "B_3") (pintype "passive"))
      (node (ref "R24") (pin "2") (pinfunction "2_2") (pintype "passive"))
    )
    (net (code "30") (name "Net-(IC5D-OUT)") (class "Default")
      (node (ref "IC5") (pin "14") (pinfunction "OUT_14") (pintype "output"))
      (node (ref "R24") (pin "1") (pinfunction "1_1") (pintype "passive"))
      (node (ref "R25") (pin "2") (pinfunction "2_2") (pintype "passive"))
    )
    (net (code "31") (name "Net-(IC6B--IN)") (class "Default")
      (node (ref "C20") (pin "2") (pinfunction "2_2") (pintype "passive"))
      (node (ref "IC6") (pin "6") (pinfunction "-IN_6") (pintype "input"))
      (node (ref "POT100") (pin "1") (pinfunction "A_1") (pintype "passive"))
      (node (ref "R100") (pin "P$1") (pinfunction "E_P$1") (pintype "passive"))
      (node (ref "R17") (pin "1") (pinfunction "1_1") (pintype "passive"))
      (node (ref "R22") (pin "2") (pinfunction "2_2") (pintype "passive"))
      (node (ref "R26") (pin "1") (pinfunction "1_1") (pintype "passive"))
    )
    (net (code "32") (name "Net-(IC6B-OUT)") (class "Default")
      (node (ref "C20") (pin "1") (pinfunction "1_1") (pintype "passive"))
      (node (ref "IC6") (pin "7") (pinfunction "OUT_7") (pintype "output"))
      (node (ref "R19") (pin "2") (pinfunction "2_2") (pintype "passive"))
      (node (ref "R20") (pin "2") (pinfunction "2_2") (pintype "passive"))
      (node (ref "R22") (pin "1") (pinfunction "1_1") (pintype "passive"))
      (node (ref "R23") (pin "2") (pinfunction "2_2") (pintype "passive"))
    )
    (net (code "33") (name "Net-(IC6C-+IN)") (class "Default")
      (node (ref "IC6") (pin "10") (pinfunction "+IN_10") (pintype "input"))
      (node (ref "R16") (pin "1") (pinfunction "1_1") (pintype "passive"))
      (node (ref "R20") (pin "1") (pinfunction "1_1") (pintype "passive"))
    )
    (net (code "34") (name "Net-(IC6C--IN)") (class "Default")
      (node (ref "IC6") (pin "9") (pinfunction "-IN_9") (pintype "input"))
      (node (ref "LED100") (pin "A") (pinfunction "A_A") (pintype "passive"))
      (node (ref "R21") (pin "1") (pinfunction "1_1") (pintype "passive"))
    )
    (net (code "35") (name "Net-(IC6C-OUT)") (class "Default")
      (node (ref "IC6") (pin "8") (pinfunction "OUT_8") (pintype "output"))
      (node (ref "LED100") (pin "K") (pinfunction "C_K") (pintype "passive"))
    )
    (net (code "36") (name "Net-(IC6D--IN)") (class "Default")
      (node (ref "IC6") (pin "13") (pinfunction "-IN_13") (pintype "input"))
      (node (ref "POT100") (pin "3") (pinfunction "B_3") (pintype "passive"))
      (node (ref "R14") (pin "2") (pinfunction "2_2") (pintype "passive"))
    )
    (net (code "37") (name "Net-(IC6D-OUT)") (class "Default")
      (node (ref "IC6") (pin "14") (pinfunction "OUT_14") (pintype "output"))
      (node (ref "R14") (pin "1") (pinfunction "1_1") (pintype "passive"))
      (node (ref "R17") (pin "2") (pinfunction "2_2") (pintype "passive"))
    )
    (net (code "38") (name "Net-(IC7A-OUT)") (class "Default")
      (node (ref "IC7") (pin "1") (pinfunction "OUT_1") (pintype "output"))
      (node (ref "R34") (pin "2") (pinfunction "2_2") (pintype "passive"))
      (node (ref "R35") (pin "1") (pinfunction "1_1") (pintype "passive"))
    )
    (net (code "39") (name "Net-(IC7B--IN)") (class "Default")
      (node (ref "C25") (pin "1") (pinfunction "1_1") (pintype "passive"))
      (node (ref "IC7") (pin "6") (pinfunction "-IN_6") (pintype "input"))
      (node (ref "R23") (pin "1") (pinfunction "1_1") (pintype "passive"))
      (node (ref "R34") (pin "1") (pinfunction "1_1") (pintype "passive"))
      (node (ref "R36") (pin "2") (pinfunction "2_2") (pintype "passive"))
      (node (ref "R40") (pin "1") (pinfunction "1_1") (pintype "passive"))
    )
    (net (code "40") (name "Net-(IC7B-OUT)") (class "Default")
      (node (ref "C25") (pin "2") (pinfunction "2_2") (pintype "passive"))
      (node (ref "IC7") (pin "7") (pinfunction "OUT_7") (pintype "output"))
      (node (ref "R36") (pin "1") (pinfunction "1_1") (pintype "passive"))
      (node (ref "R37") (pin "2") (pinfunction "2_2") (pintype "passive"))
      (node (ref "R57") (pin "2") (pinfunction "2_2") (pintype "passive"))
    )
    (net (code "41") (name "Net-(IC7C-+IN)") (class "Default")
      (node (ref "IC7") (pin "10") (pinfunction "+IN_10") (pintype "input"))
      (node (ref "R37") (pin "1") (pinfunction "1_1") (pintype "passive"))
      (node (ref "R39") (pin "1") (pinfunction "1_1") (pintype "passive"))
    )
    (net (code "42") (name "Net-(IC7C--IN)") (class "Default")
      (node (ref "IC7") (pin "9") (pinfunction "-IN_9") (pintype "input"))
      (node (ref "LED102") (pin "A") (pinfunction "A_A") (pintype "passive"))
      (node (ref "R38") (pin "1") (pinfunction "1_1") (pintype "passive"))
    )
    (net (code "43") (name "Net-(IC7C-OUT)") (class "Default")
      (node (ref "IC7") (pin "8") (pinfunction "OUT_8") (pintype "output"))
      (node (ref "LED102") (pin "K") (pinfunction "C_K") (pintype "passive"))
    )
    (net (code "44") (name "Net-(IC7D--IN)") (class "Default")
      (node (ref "IC7") (pin "13") (pinfunction "-IN_13") (pintype "input"))
      (node (ref "R33") (pin "2") (pinfunction "2_2") (pintype "passive"))
      (node (ref "R56") (pin "1") (pinfunction "1_1") (pintype "passive"))
    )
    (net (code "45") (name "Net-(IC8A-OUT)") (class "Default")
      (node (ref "IC8") (pin "1") (pinfunction "OUT_1") (pintype "output"))
      (node (ref "R41") (pin "1") (pinfunction "1_1") (pintype "passive"))
      (node (ref "R45") (pin "2") (pinfunction "2_2") (pintype "passive"))
    )
    (net (code "46") (name "Net-(IC8B--IN)") (class "Default")
      (node (ref "C28") (pin "1") (pinfunction "1_1") (pintype "passive"))
      (node (ref "IC8") (pin "6") (pinfunction "-IN_6") (pintype "input"))
      (node (ref "R31") (pin "1") (pinfunction "1_1") (pintype "passive"))
      (node (ref "R32") (pin "1") (pinfunction "1_1") (pintype "passive"))
      (node (ref "R45") (pin "1") (pinfunction "1_1") (pintype "passive"))
      (node (ref "R46") (pin "2") (pinfunction "2_2") (pintype "passive"))
    )
    (net (code "47") (name "Net-(IC8B-OUT)") (class "Default")
      (node (ref "C28") (pin "2") (pinfunction "2_2") (pintype "passive"))
      (node (ref "IC8") (pin "7") (pinfunction "OUT_7") (pintype "output"))
      (node (ref "R46") (pin "1") (pinfunction "1_1") (pintype "passive"))
      (node (ref "R51") (pin "2") (pinfunction "2_2") (pintype "passive"))
      (node (ref "R58") (pin "2") (pinfunction "2_2") (pintype "passive"))
    )
    (net (code "48") (name "Net-(IC8C-+IN)") (class "Default")
      (node (ref "IC8") (pin "10") (pinfunction "+IN_10") (pintype "input"))
      (node (ref "R50") (pin "1") (pinfunction "1_1") (pintype "passive"))
      (node (ref "R51") (pin "1") (pinfunction "1_1") (pintype "passive"))
    )
    (net (code "49") (name "Net-(IC8C--IN)") (class "Default")
      (node (ref "IC8") (pin "9") (pinfunction "-IN_9") (pintype "input"))
      (node (ref "LED103") (pin "A") (pinfunction "A_A") (pintype "passive"))
      (node (ref "R47") (pin "1") (pinfunction "1_1") (pintype "passive"))
    )
    (net (code "50") (name "Net-(IC8C-OUT)") (class "Default")
      (node (ref "IC8") (pin "8") (pinfunction "OUT_8") (pintype "output"))
      (node (ref "LED103") (pin "K") (pinfunction "C_K") (pintype "passive"))
    )
    (net (code "51") (name "Net-(IC8D--IN)") (class "Default")
      (node (ref "IC8") (pin "13") (pinfunction "-IN_13") (pintype "input"))
      (node (ref "R42") (pin "2") (pinfunction "2_2") (pintype "passive"))
      (node (ref "R55") (pin "1") (pinfunction "1_1") (pintype "passive"))
    )
    (net (code "52") (name "Net-(J100-3)") (class "Default")
      (node (ref "J100") (pin "P3") (pinfunction "3_P3") (pintype "passive"))
      (node (ref "R44") (pin "2") (pinfunction "2_2") (pintype "passive"))
    )
    (net (code "53") (name "Net-(J101-3)") (class "Default")
      (node (ref "J101") (pin "P3") (pinfunction "3_P3") (pintype "passive"))
      (node (ref "R43") (pin "2") (pinfunction "2_2") (pintype "passive"))
    )
    (net (code "54") (name "Net-(J102-2)") (class "Default")
      (node (ref "J102") (pin "P2") (pinfunction "2_P2") (pintype "passive"))
      (node (ref "R54") (pin "2") (pinfunction "2_2") (pintype "passive"))
    )
    (net (code "55") (name "Net-(J102-3)") (class "Default")
      (node (ref "J102") (pin "P3") (pinfunction "3_P3") (pintype "passive"))
      (node (ref "R48") (pin "2") (pinfunction "2_2") (pintype "passive"))
    )
    (net (code "56") (name "Net-(J103-2)") (class "Default")
      (node (ref "J103") (pin "P2") (pinfunction "2_P2") (pintype "passive"))
      (node (ref "R53") (pin "2") (pinfunction "2_2") (pintype "passive"))
    )
    (net (code "57") (name "Net-(J103-3)") (class "Default")
      (node (ref "J103") (pin "P3") (pinfunction "3_P3") (pintype "passive"))
      (node (ref "R49") (pin "2") (pinfunction "2_2") (pintype "passive"))
    )
    (net (code "58") (name "Net-(J104-2)") (class "Default")
      (node (ref "J104") (pin "P2") (pinfunction "2_P2") (pintype "passive"))
      (node (ref "R56") (pin "2") (pinfunction "2_2") (pintype "passive"))
    )
    (net (code "59") (name "Net-(J104-3)") (class "Default")
      (node (ref "J104") (pin "P3") (pinfunction "3_P3") (pintype "passive"))
      (node (ref "R57") (pin "1") (pinfunction "1_1") (pintype "passive"))
    )
    (net (code "60") (name "Net-(J105-2)") (class "Default")
      (node (ref "J105") (pin "P2") (pinfunction "2_P2") (pintype "passive"))
      (node (ref "R55") (pin "2") (pinfunction "2_2") (pintype "passive"))
    )
    (net (code "61") (name "Net-(J105-3)") (class "Default")
      (node (ref "J105") (pin "P3") (pinfunction "3_P3") (pintype "passive"))
      (node (ref "R58") (pin "1") (pinfunction "1_1") (pintype "passive"))
    )
    (net (code "62") (name "Net-(JP1-Pad10)") (class "Default")
      (node (ref "JP1") (pin "10") (pinfunction "10_10") (pintype "passive"))
      (node (ref "JP1") (pin "9") (pinfunction "9_9") (pintype "passive"))
      (node (ref "P1") (pin "2") (pinfunction "2_2") (pintype "bidirectional"))
    )
    (net (code "63") (name "Net-(L1-Pad2)") (class "Default")
      (node (ref "L1") (pin "2") (pinfunction "2_2") (pintype "passive"))
      (node (ref "P1") (pin "1") (pinfunction "1_1") (pintype "bidirectional"))
    )
    (net (code "64") (name "Net-(POT100-W)") (class "Default")
      (node (ref "POT100") (pin "2") (pinfunction "W_2") (pintype "passive"))
      (node (ref "R44") (pin "1") (pinfunction "1_1") (pintype "passive"))
    )
    (net (code "65") (name "Net-(POT101-W)") (class "Default")
      (node (ref "POT101") (pin "2") (pinfunction "W_2") (pintype "passive"))
      (node (ref "R43") (pin "1") (pinfunction "1_1") (pintype "passive"))
    )
    (net (code "66") (name "Net-(R100-S)") (class "Default")
      (node (ref "R100") (pin "P$2") (pinfunction "S_P$2") (pintype "passive"))
      (node (ref "R2") (pin "1") (pinfunction "1_1") (pintype "passive"))
    )
    (net (code "67") (name "Net-(R101-S)") (class "Default")
      (node (ref "R101") (pin "P$2") (pinfunction "S_P$2") (pintype "passive"))
      (node (ref "R12") (pin "1") (pinfunction "1_1") (pintype "passive"))
    )
    (net (code "68") (name "OUT") (class "Default")
      (node (ref "IC8") (pin "14") (pinfunction "OUT_14") (pintype "output"))
      (node (ref "J1") (pin "1") (pinfunction "1_1") (pintype "passive"))
      (node (ref "R42") (pin "1") (pinfunction "1_1") (pintype "passive"))
    )
    (net (code "69") (name "VCC") (class "Default")
      (node (ref "C1") (pin "1") (pinfunction "1_1") (pintype "passive"))
      (node (ref "C16") (pin "1") (pinfunction "1_1") (pintype "passive"))
      (node (ref "C18") (pin "1") (pinfunction "1_1") (pintype "passive"))
      (node (ref "C23") (pin "1") (pinfunction "1_1") (pintype "passive"))
      (node (ref "C26") (pin "1") (pinfunction "1_1") (pintype "passive"))
      (node (ref "C4") (pin "+") (pinfunction "+_+") (pintype "passive"))
      (node (ref "C7") (pin "1") (pinfunction "1_1") (pintype "passive"))
      (node (ref "C8") (pin "1") (pinfunction "1_1") (pintype "passive"))
      (node (ref "IC3") (pin "16") (pinfunction "V+_16") (pintype "power_in"))
      (node (ref "IC4") (pin "16") (pinfunction "V+_16") (pintype "power_in"))
      (node (ref "IC5") (pin "4") (pinfunction "V+_4") (pintype "power_in"))
      (node (ref "IC6") (pin "4") (pinfunction "V+_4") (pintype "power_in"))
      (node (ref "IC7") (pin "4") (pinfunction "V+_4") (pintype "power_in"))
      (node (ref "IC8") (pin "4") (pinfunction "V+_4") (pintype "power_in"))
      (node (ref "L2") (pin "1") (pinfunction "1_1") (pintype "passive"))
      (node (ref "R3") (pin "1") (pinfunction "1_1") (pintype "passive"))
      (node (ref "R4") (pin "1") (pinfunction "1_1") (pintype "passive"))
      (node (ref "R5") (pin "1") (pinfunction "1_1") (pintype "passive"))
    )
    (net (code "70") (name "VEE") (class "Default")
      (node (ref "C10") (pin "2") (pinfunction "2_2") (pintype "passive"))
      (node (ref "C14") (pin "2") (pinfunction "2_2") (pintype "passive"))
      (node (ref "C17") (pin "2") (pinfunction "2_2") (pintype "passive"))
      (node (ref "C24") (pin "2") (pinfunction "2_2") (pintype "passive"))
      (node (ref "C27") (pin "2") (pinfunction "2_2") (pintype "passive"))
      (node (ref "C3") (pin "1") (pinfunction "1_1") (pintype "passive"))
      (node (ref "C6") (pin "-") (pinfunction "-_-") (pintype "passive"))
      (node (ref "C9") (pin "2") (pinfunction "2_2") (pintype "passive"))
      (node (ref "D2") (pin "A") (pinfunction "A_A") (pintype "passive"))
      (node (ref "IC3") (pin "9") (pinfunction "V-_9") (pintype "power_in"))
      (node (ref "IC4") (pin "9") (pinfunction "V-_9") (pintype "power_in"))
      (node (ref "IC5") (pin "11") (pinfunction "V-_11") (pintype "power_in"))
      (node (ref "IC6") (pin "11") (pinfunction "V-_11") (pintype "power_in"))
      (node (ref "IC7") (pin "11") (pinfunction "V-_11") (pintype "power_in"))
      (node (ref "IC8") (pin "11") (pinfunction "V-_11") (pintype "power_in"))
      (node (ref "L1") (pin "1") (pinfunction "1_1") (pintype "passive"))
      (node (ref "R1") (pin "1") (pinfunction "1_1") (pintype "passive"))
    )
  )
)
